# FT232.net
KiCad netlist of a schematic drawn in EAGLE
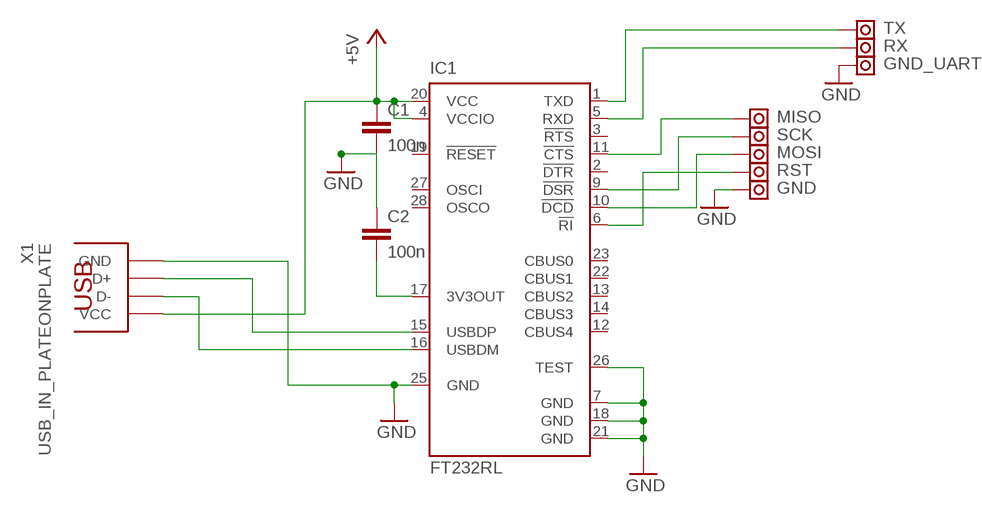
[diagram p0: schematic, sheet 1]

(export (version "E")
  (design (tool "Eeschema 10.0.6"))
  (components
    (comp (ref "C1")
      (value "100n")
      (footprint "eagle-import:C0805")
      (libsource (lib "eagle-import") (part "C-EUC0805"))
    )
    (comp (ref "C2")
      (value "100n")
      (footprint "eagle-import:0805")
      (libsource (lib "eagle-import") (part "C0805"))
    )
    (comp (ref "GND")
      (value "PAD")
      (footprint "eagle-import:PAD")
      (libsource (lib "eagle-import") (part "PAD"))
    )
    (comp (ref "GND_UART")
      (value "PAD")
      (footprint "eagle-import:PAD")
      (libsource (lib "eagle-import") (part "PAD"))
    )
    (comp (ref "IC1")
      (value "FT232RL")
      (footprint "eagle-import:SSOP28")
      (libsource (lib "eagle-import") (part "FT232RL"))
    )
    (comp (ref "MISO")
      (value "PAD")
      (footprint "eagle-import:PAD")
      (libsource (lib "eagle-import") (part "PAD"))
    )
    (comp (ref "MOSI")
      (value "PAD")
      (footprint "eagle-import:PAD")
      (libsource (lib "eagle-import") (part "PAD"))
    )
    (comp (ref "RST")
      (value "PAD")
      (footprint "eagle-import:PAD")
      (libsource (lib "eagle-import") (part "PAD"))
    )
    (comp (ref "RX")
      (value "PAD")
      (footprint "eagle-import:PAD")
      (libsource (lib "eagle-import") (part "PAD"))
    )
    (comp (ref "SCK")
      (value "PAD")
      (footprint "eagle-import:PAD")
      (libsource (lib "eagle-import") (part "PAD"))
    )
    (comp (ref "TX")
      (value "PAD")
      (footprint "eagle-import:PAD")
      (libsource (lib "eagle-import") (part "PAD"))
    )
    (comp (ref "X1")
      (value "USB_IN_PLATEONPLATE")
      (footprint "eagle-import:USB_IN_PLATE")
      (libsource (lib "eagle-import") (part "USB_IN_PLATEONPLATE"))
    )
  )
  (nets
    (net (code "1") (name "+5V") (class "Default")
      (node (ref "C1") (pin "1") (pinfunction "1_1") (pintype "passive"))
      (node (ref "IC1") (pin "20") (pinfunction "VCC_20") (pintype "power_in"))
      (node (ref "IC1") (pin "4") (pinfunction "VCCIO_4") (pintype "power_in"))
      (node (ref "X1") (pin "VCC") (pinfunction "VCC_VCC") (pintype "power_in"))
    )
    (net (code "2") (name "GND") (class "Default")
      (node (ref "C1") (pin "2") (pinfunction "2_2") (pintype "passive"))
      (node (ref "C2") (pin "1") (pinfunction "1_1") (pintype "passive"))
      (node (ref "GND") (pin "P$1") (pinfunction "PAD_P$1") (pintype "bidirectional"))
      (node (ref "GND_UART") (pin "P$1") (pinfunction "PAD_P$1") (pintype "bidirectional"))
      (node (ref "IC1") (pin "18") (pinfunction "GND_18") (pintype "power_in"))
      (node (ref "IC1") (pin "21") (pinfunction "GND_21") (pintype "power_in"))
      (node (ref "IC1") (pin "25") (pinfunction "GND_25") (pintype "power_in"))
      (node (ref "IC1") (pin "26") (pinfunction "TEST_26") (pintype "input"))
      (node (ref "IC1") (pin "7") (pinfunction "GND_7") (pintype "power_in"))
      (node (ref "X1") (pin "GND") (pinfunction "GND_GND") (pintype "power_in"))
    )
    (net (code "3") (name "Net-(IC1-3V3OUT)") (class "Default")
      (node (ref "C2") (pin "2") (pinfunction "2_2") (pintype "passive"))
      (node (ref "IC1") (pin "17") (pinfunction "3V3OUT_17") (pintype "output"))
    )
    (net (code "4") (name "Net-(IC1-RXD)") (class "Default")
      (node (ref "IC1") (pin "5") (pinfunction "RXD_5") (pintype "input"))
      (node (ref "RX") (pin "P$1") (pinfunction "PAD_P$1") (pintype "bidirectional"))
    )
    (net (code "5") (name "Net-(IC1-TXD)") (class "Default")
      (node (ref "IC1") (pin "1") (pinfunction "TXD_1") (pintype "output"))
      (node (ref "TX") (pin "P$1") (pinfunction "PAD_P$1") (pintype "bidirectional"))
    )
    (net (code "6") (name "Net-(IC1-USBDM)") (class "Default")
      (node (ref "IC1") (pin "16") (pinfunction "USBDM_16") (pintype "bidirectional"))
      (node (ref "X1") (pin "D-") (pinfunction "D-_D-") (pintype "bidirectional"))
    )
    (net (code "7") (name "Net-(IC1-USBDP)") (class "Default")
      (node (ref "IC1") (pin "15") (pinfunction "USBDP_15") (pintype "bidirectional"))
      (node (ref "X1") (pin "D+") (pinfunction "D+_D+") (pintype "bidirectional"))
    )
    (net (code "8") (name "Net-(IC1-~{CTS})") (class "Default")
      (node (ref "IC1") (pin "11") (pinfunction "~{CTS}_11") (pintype "input"))
      (node (ref "MISO") (pin "P$1") (pinfunction "PAD_P$1") (pintype "bidirectional"))
    )
    (net (code "9") (name "Net-(IC1-~{DCD})") (class "Default")
      (node (ref "IC1") (pin "10") (pinfunction "~{DCD}_10") (pintype "input"))
      (node (ref "MOSI") (pin "P$1") (pinfunction "PAD_P$1") (pintype "bidirectional"))
    )
    (net (code "10") (name "Net-(IC1-~{DSR})") (class "Default")
      (node (ref "IC1") (pin "9") (pinfunction "~{DSR}_9") (pintype "input"))
      (node (ref "SCK") (pin "P$1") (pinfunction "PAD_P$1") (pintype "bidirectional"))
    )
    (net (code "11") (name "Net-(IC1-~{RI})") (class "Default")
      (node (ref "IC1") (pin "6") (pinfunction "~{RI}_6") (pintype "input"))
      (node (ref "RST") (pin "P$1") (pinfunction "PAD_P$1") (pintype "bidirectional"))
    )
    (net (code "12") (name "unconnected-(IC1-CBUS0-Pad23)") (class "Default")
      (node (ref "IC1") (pin "23") (pinfunction "CBUS0_23") (pintype "bidirectional"))
    )
    (net (code "13") (name "unconnected-(IC1-CBUS1-Pad22)") (class "Default")
      (node (ref "IC1") (pin "22") (pinfunction "CBUS1_22") (pintype "bidirectional"))
    )
    (net (code "14") (name "unconnected-(IC1-CBUS2-Pad13)") (class "Default")
      (node (ref "IC1") (pin "13") (pinfunction "CBUS2_13") (pintype "bidirectional"))
    )
    (net (code "15") (name "unconnected-(IC1-CBUS3-Pad14)") (class "Default")
      (node (ref "IC1") (pin "14") (pinfunction "CBUS3_14") (pintype "bidirectional"))
    )
    (net (code "16") (name "unconnected-(IC1-CBUS4-Pad12)") (class "Default")
      (node (ref "IC1") (pin "12") (pinfunction "CBUS4_12") (pintype "bidirectional"))
    )
    (net (code "17") (name "unconnected-(IC1-OSCI-Pad27)") (class "Default")
      (node (ref "IC1") (pin "27") (pinfunction "OSCI_27") (pintype "input"))
    )
    (net (code "18") (name "unconnected-(IC1-OSCO-Pad28)") (class "Default")
      (node (ref "IC1") (pin "28") (pinfunction "OSCO_28") (pintype "output"))
    )
    (net (code "19") (name "unconnected-(IC1-~{DTR}-Pad2)") (class "Default")
      (node (ref "IC1") (pin "2") (pinfunction "~{DTR}_2") (pintype "output"))
    )
    (net (code "20") (name "unconnected-(IC1-~{RESET}-Pad19)") (class "Default")
      (node (ref "IC1") (pin "19") (pinfunction "~{RESET}_19") (pintype "input"))
    )
    (net (code "21") (name "unconnected-(IC1-~{RTS}-Pad3)") (class "Default")
      (node (ref "IC1") (pin "3") (pinfunction "~{RTS}_3") (pintype "output"))
    )
  )
)
